# DAQAccel.net
KiCad netlist of a schematic drawn in EAGLE
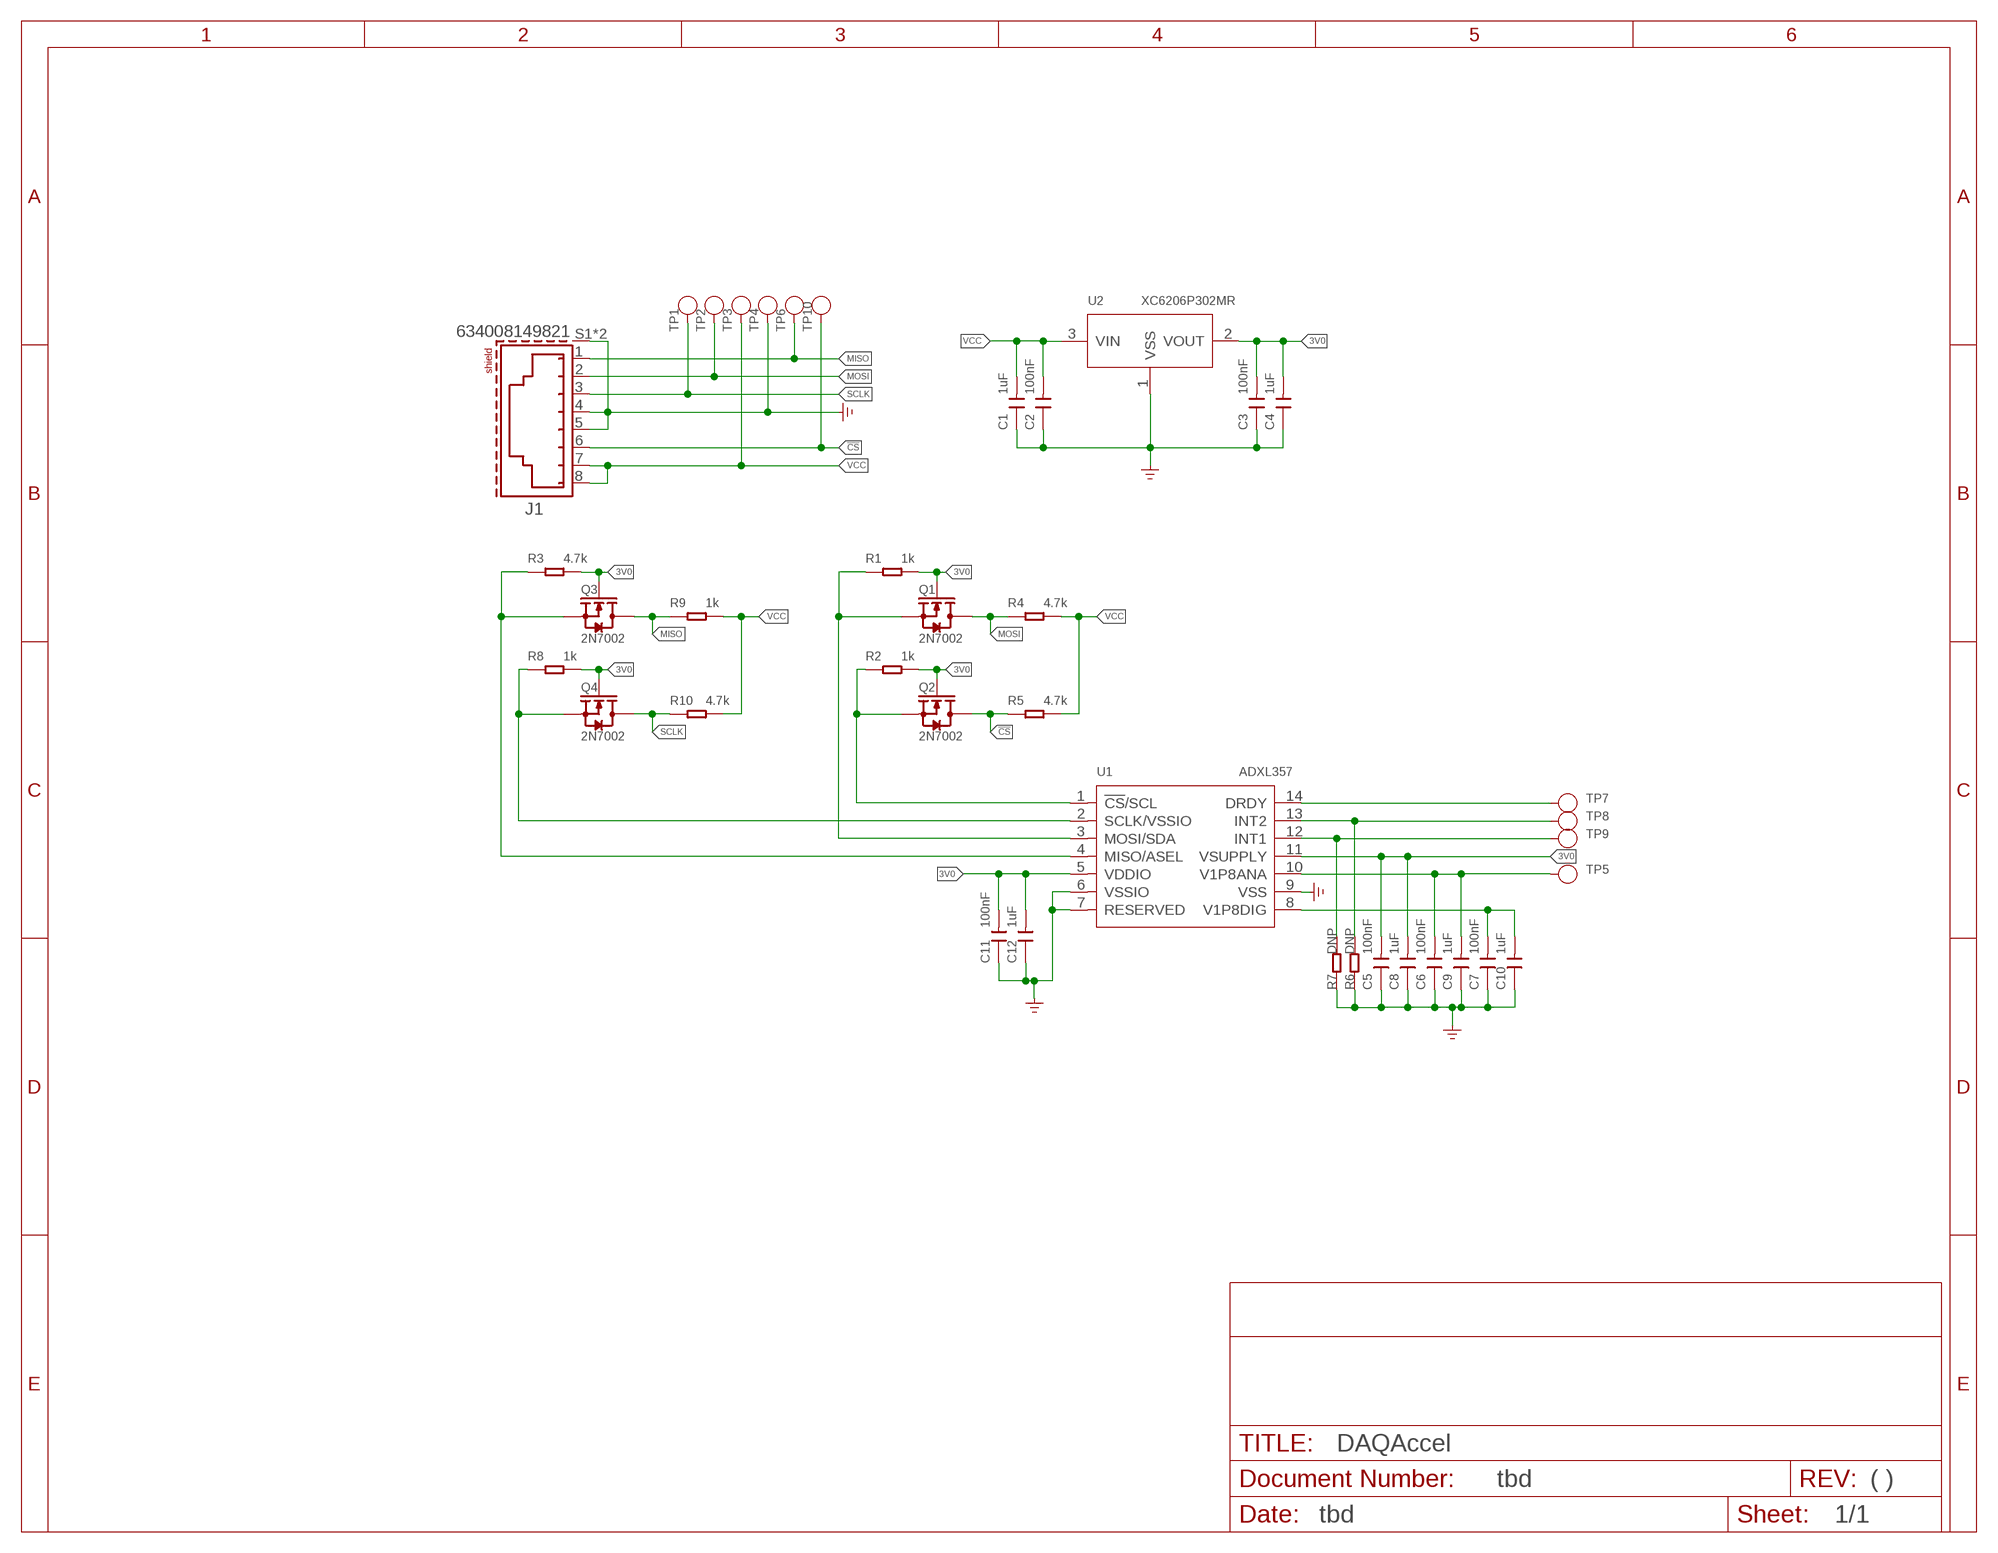
[diagram p0: schematic, sheet 1]

(export (version "E")
  (design (tool "Eeschema 10.0.6"))
  (components
    (comp (ref "C1")
      (value "1uF")
      (footprint "eagle-import:C0603")
      (libsource (lib "eagle-import") (part "CAP-0603"))
    )
    (comp (ref "C2")
      (value "100nF")
      (footprint "eagle-import:C0603")
      (libsource (lib "eagle-import") (part "CAP-0603"))
    )
    (comp (ref "C3")
      (value "100nF")
      (footprint "eagle-import:C0603")
      (libsource (lib "eagle-import") (part "CAP-0603"))
    )
    (comp (ref "C4")
      (value "1uF")
      (footprint "eagle-import:C0603")
      (libsource (lib "eagle-import") (part "CAP-0603"))
    )
    (comp (ref "C5")
      (value "100nF")
      (footprint "eagle-import:C0603")
      (libsource (lib "eagle-import") (part "CAP-0603"))
    )
    (comp (ref "C6")
      (value "100nF")
      (footprint "eagle-import:C0603")
      (libsource (lib "eagle-import") (part "CAP-0603"))
    )
    (comp (ref "C7")
      (value "100nF")
      (footprint "eagle-import:C0603")
      (libsource (lib "eagle-import") (part "CAP-0603"))
    )
    (comp (ref "C8")
      (value "1uF")
      (footprint "eagle-import:C0603")
      (libsource (lib "eagle-import") (part "CAP-0603"))
    )
    (comp (ref "C9")
      (value "1uF")
      (footprint "eagle-import:C0603")
      (libsource (lib "eagle-import") (part "CAP-0603"))
    )
    (comp (ref "C10")
      (value "1uF")
      (footprint "eagle-import:C0603")
      (libsource (lib "eagle-import") (part "CAP-0603"))
    )
    (comp (ref "C11")
      (value "100nF")
      (footprint "eagle-import:C0603")
      (libsource (lib "eagle-import") (part "CAP-0603"))
    )
    (comp (ref "C12")
      (value "1uF")
      (footprint "eagle-import:C0603")
      (libsource (lib "eagle-import") (part "CAP-0603"))
    )
    (comp (ref "J1")
      (value "634008149821")
      (footprint "eagle-import:634008149821")
      (libsource (lib "eagle-import") (part "634008149821"))
    )
    (comp (ref "Q1")
      (value "2N7002")
      (footprint "eagle-import:SOT-23")
      (libsource (lib "eagle-import") (part "MOSFET-N'SOT23'"))
    )
    (comp (ref "Q2")
      (value "2N7002")
      (footprint "eagle-import:SOT-23")
      (libsource (lib "eagle-import") (part "MOSFET-N'SOT23'"))
    )
    (comp (ref "Q3")
      (value "2N7002")
      (footprint "eagle-import:SOT-23")
      (libsource (lib "eagle-import") (part "MOSFET-N'SOT23'"))
    )
    (comp (ref "Q4")
      (value "2N7002")
      (footprint "eagle-import:SOT-23")
      (libsource (lib "eagle-import") (part "MOSFET-N'SOT23'"))
    )
    (comp (ref "R1")
      (value "1k")
      (footprint "eagle-import:R0603")
      (libsource (lib "eagle-import") (part "RES-0603"))
    )
    (comp (ref "R2")
      (value "1k")
      (footprint "eagle-import:R0603")
      (libsource (lib "eagle-import") (part "RES-0603"))
    )
    (comp (ref "R3")
      (value "4.7k")
      (footprint "eagle-import:R0603")
      (libsource (lib "eagle-import") (part "RES-0603"))
    )
    (comp (ref "R4")
      (value "4.7k")
      (footprint "eagle-import:R0603")
      (libsource (lib "eagle-import") (part "RES-0603"))
    )
    (comp (ref "R5")
      (value "4.7k")
      (footprint "eagle-import:R0603")
      (libsource (lib "eagle-import") (part "RES-0603"))
    )
    (comp (ref "R6")
      (value "DNP")
      (footprint "eagle-import:R0603")
      (libsource (lib "eagle-import") (part "RES-0603"))
    )
    (comp (ref "R7")
      (value "DNP")
      (footprint "eagle-import:R0603")
      (libsource (lib "eagle-import") (part "RES-0603"))
    )
    (comp (ref "R8")
      (value "1k")
      (footprint "eagle-import:R0603")
      (libsource (lib "eagle-import") (part "RES-0603"))
    )
    (comp (ref "R9")
      (value "1k")
      (footprint "eagle-import:R0603")
      (libsource (lib "eagle-import") (part "RES-0603"))
    )
    (comp (ref "R10")
      (value "4.7k")
      (footprint "eagle-import:R0603")
      (libsource (lib "eagle-import") (part "RES-0603"))
    )
    (comp (ref "TP1")
      (value "Test")
      (footprint "eagle-import:TP-D45MIL")
      (fields (field (name "PARTNO") "DNP"))
      (libsource (lib "eagle-import") (part "TEST-POINT'4545'"))
    )
    (comp (ref "TP2")
      (value "Test")
      (footprint "eagle-import:TP-D45MIL")
      (fields (field (name "PARTNO") "DNP"))
      (libsource (lib "eagle-import") (part "TEST-POINT'4545'"))
    )
    (comp (ref "TP3")
      (value "Test")
      (footprint "eagle-import:TP-D45MIL")
      (fields (field (name "PARTNO") "DNP"))
      (libsource (lib "eagle-import") (part "TEST-POINT'4545'"))
    )
    (comp (ref "TP4")
      (value "Test")
      (footprint "eagle-import:TP-D45MIL")
      (fields (field (name "PARTNO") "DNP"))
      (libsource (lib "eagle-import") (part "TEST-POINT'4545'"))
    )
    (comp (ref "TP5")
      (value "Test")
      (footprint "eagle-import:TP-D45MIL")
      (fields (field (name "PARTNO") "DNP"))
      (libsource (lib "eagle-import") (part "TEST-POINT'4545'"))
    )
    (comp (ref "TP6")
      (value "Test")
      (footprint "eagle-import:TP-D45MIL")
      (fields (field (name "PARTNO") "DNP"))
      (libsource (lib "eagle-import") (part "TEST-POINT'4545'"))
    )
    (comp (ref "TP7")
      (value "Test")
      (footprint "eagle-import:TP-D45MIL")
      (fields (field (name "PARTNO") "DNP"))
      (libsource (lib "eagle-import") (part "TEST-POINT'4545'"))
    )
    (comp (ref "TP8")
      (value "Test")
      (footprint "eagle-import:TP-D45MIL")
      (fields (field (name "PARTNO") "DNP"))
      (libsource (lib "eagle-import") (part "TEST-POINT'4545'"))
    )
    (comp (ref "TP9")
      (value "Test")
      (footprint "eagle-import:TP-D45MIL")
      (fields (field (name "PARTNO") "DNP"))
      (libsource (lib "eagle-import") (part "TEST-POINT'4545'"))
    )
    (comp (ref "TP10")
      (value "Test")
      (footprint "eagle-import:TP-D45MIL")
      (fields (field (name "PARTNO") "DNP"))
      (libsource (lib "eagle-import") (part "TEST-POINT'4545'"))
    )
    (comp (ref "U1")
      (value "ADXL357")
      (footprint "eagle-import:LCC-14-TERMINAL")
      (libsource (lib "eagle-import") (part "SENSOR-ADXL357BEZ"))
    )
    (comp (ref "U2")
      (value "XC6206P302MR")
      (footprint "eagle-import:SOT-23")
      (libsource (lib "eagle-import") (part "PMIC-XC6206PMR"))
    )
  )
  (nets
    (net (code "1") (name "/~{CS}") (class "Default")
      (node (ref "J1") (pin "6") (pinfunction "6_6") (pintype "passive"))
      (node (ref "Q2") (pin "3") (pinfunction "D_3") (pintype "passive"))
      (node (ref "R5") (pin "1") (pinfunction "1_1") (pintype "passive"))
      (node (ref "TP10") (pin "T") (pinfunction "T_T") (pintype "bidirectional"))
    )
    (net (code "2") (name "3V0") (class "Default")
      (node (ref "C11") (pin "2") (pinfunction "2_2") (pintype "passive"))
      (node (ref "C12") (pin "2") (pinfunction "2_2") (pintype "passive"))
      (node (ref "C3") (pin "2") (pinfunction "2_2") (pintype "passive"))
      (node (ref "C4") (pin "2") (pinfunction "2_2") (pintype "passive"))
      (node (ref "C5") (pin "2") (pinfunction "2_2") (pintype "passive"))
      (node (ref "C8") (pin "2") (pinfunction "2_2") (pintype "passive"))
      (node (ref "Q1") (pin "1") (pinfunction "G_1") (pintype "passive"))
      (node (ref "Q2") (pin "1") (pinfunction "G_1") (pintype "passive"))
      (node (ref "Q3") (pin "1") (pinfunction "G_1") (pintype "passive"))
      (node (ref "Q4") (pin "1") (pinfunction "G_1") (pintype "passive"))
      (node (ref "R1") (pin "2") (pinfunction "2_2") (pintype "passive"))
      (node (ref "R2") (pin "2") (pinfunction "2_2") (pintype "passive"))
      (node (ref "R3") (pin "2") (pinfunction "2_2") (pintype "passive"))
      (node (ref "R8") (pin "2") (pinfunction "2_2") (pintype "passive"))
      (node (ref "U1") (pin "11") (pinfunction "VSUPPLY_11") (pintype "bidirectional"))
      (node (ref "U1") (pin "5") (pinfunction "VDDIO_5") (pintype "bidirectional"))
      (node (ref "U2") (pin "2") (pinfunction "VOUT_2") (pintype "bidirectional"))
    )
    (net (code "3") (name "GND_POWER") (class "Default")
      (node (ref "C1") (pin "1") (pinfunction "1_1") (pintype "passive"))
      (node (ref "C10") (pin "1") (pinfunction "1_1") (pintype "passive"))
      (node (ref "C11") (pin "1") (pinfunction "1_1") (pintype "passive"))
      (node (ref "C12") (pin "1") (pinfunction "1_1") (pintype "passive"))
      (node (ref "C2") (pin "1") (pinfunction "1_1") (pintype "passive"))
      (node (ref "C3") (pin "1") (pinfunction "1_1") (pintype "passive"))
      (node (ref "C4") (pin "1") (pinfunction "1_1") (pintype "passive"))
      (node (ref "C5") (pin "1") (pinfunction "1_1") (pintype "passive"))
      (node (ref "C6") (pin "1") (pinfunction "1_1") (pintype "passive"))
      (node (ref "C7") (pin "1") (pinfunction "1_1") (pintype "passive"))
      (node (ref "C8") (pin "1") (pinfunction "1_1") (pintype "passive"))
      (node (ref "C9") (pin "1") (pinfunction "1_1") (pintype "passive"))
      (node (ref "J1") (pin "4") (pinfunction "4_4") (pintype "passive"))
      (node (ref "J1") (pin "5") (pinfunction "5_5") (pintype "passive"))
      (node (ref "J1") (pin "S1") (pinfunction "SHIELD_S1") (pintype "passive"))
      (node (ref "J1") (pin "S2") (pinfunction "SHIELD_S2") (pintype "passive"))
      (node (ref "R6") (pin "1") (pinfunction "1_1") (pintype "passive"))
      (node (ref "R7") (pin "1") (pinfunction "1_1") (pintype "passive"))
      (node (ref "TP4") (pin "T") (pinfunction "T_T") (pintype "bidirectional"))
      (node (ref "U1") (pin "6") (pinfunction "VSSIO_6") (pintype "bidirectional"))
      (node (ref "U1") (pin "7") (pinfunction "RESERVED_7") (pintype "bidirectional"))
      (node (ref "U1") (pin "9") (pinfunction "VSS_9") (pintype "bidirectional"))
      (node (ref "U2") (pin "1") (pinfunction "VSS_1") (pintype "bidirectional"))
    )
    (net (code "4") (name "MISO") (class "Default")
      (node (ref "J1") (pin "1") (pinfunction "1_1") (pintype "passive"))
      (node (ref "Q3") (pin "3") (pinfunction "D_3") (pintype "passive"))
      (node (ref "R9") (pin "1") (pinfunction "1_1") (pintype "passive"))
      (node (ref "TP6") (pin "T") (pinfunction "T_T") (pintype "bidirectional"))
    )
    (net (code "5") (name "MOSI") (class "Default")
      (node (ref "J1") (pin "2") (pinfunction "2_2") (pintype "passive"))
      (node (ref "Q1") (pin "3") (pinfunction "D_3") (pintype "passive"))
      (node (ref "R4") (pin "1") (pinfunction "1_1") (pintype "passive"))
      (node (ref "TP2") (pin "T") (pinfunction "T_T") (pintype "bidirectional"))
    )
    (net (code "6") (name "Net-(Q1-S)") (class "Default")
      (node (ref "Q1") (pin "2") (pinfunction "S_2") (pintype "passive"))
      (node (ref "R1") (pin "1") (pinfunction "1_1") (pintype "passive"))
      (node (ref "U1") (pin "3") (pinfunction "MOSI/SDA_3") (pintype "bidirectional"))
    )
    (net (code "7") (name "Net-(Q2-S)") (class "Default")
      (node (ref "Q2") (pin "2") (pinfunction "S_2") (pintype "passive"))
      (node (ref "R2") (pin "1") (pinfunction "1_1") (pintype "passive"))
      (node (ref "U1") (pin "1") (pinfunction "~{CS}/SCL_1") (pintype "bidirectional"))
    )
    (net (code "8") (name "Net-(Q3-S)") (class "Default")
      (node (ref "Q3") (pin "2") (pinfunction "S_2") (pintype "passive"))
      (node (ref "R3") (pin "1") (pinfunction "1_1") (pintype "passive"))
      (node (ref "U1") (pin "4") (pinfunction "MISO/ASEL_4") (pintype "bidirectional"))
    )
    (net (code "9") (name "Net-(Q4-S)") (class "Default")
      (node (ref "Q4") (pin "2") (pinfunction "S_2") (pintype "passive"))
      (node (ref "R8") (pin "1") (pinfunction "1_1") (pintype "passive"))
      (node (ref "U1") (pin "2") (pinfunction "SCLK/VSSIO_2") (pintype "bidirectional"))
    )
    (net (code "10") (name "Net-(U1-DRDY)") (class "Default")
      (node (ref "TP7") (pin "T") (pinfunction "T_T") (pintype "bidirectional"))
      (node (ref "U1") (pin "14") (pinfunction "DRDY_14") (pintype "bidirectional"))
    )
    (net (code "11") (name "Net-(U1-INT1)") (class "Default")
      (node (ref "R7") (pin "2") (pinfunction "2_2") (pintype "passive"))
      (node (ref "TP9") (pin "T") (pinfunction "T_T") (pintype "bidirectional"))
      (node (ref "U1") (pin "12") (pinfunction "INT1_12") (pintype "bidirectional"))
    )
    (net (code "12") (name "Net-(U1-INT2)") (class "Default")
      (node (ref "R6") (pin "2") (pinfunction "2_2") (pintype "passive"))
      (node (ref "TP8") (pin "T") (pinfunction "T_T") (pintype "bidirectional"))
      (node (ref "U1") (pin "13") (pinfunction "INT2_13") (pintype "bidirectional"))
    )
    (net (code "13") (name "Net-(U1-V1P8ANA)") (class "Default")
      (node (ref "C6") (pin "2") (pinfunction "2_2") (pintype "passive"))
      (node (ref "C9") (pin "2") (pinfunction "2_2") (pintype "passive"))
      (node (ref "TP5") (pin "T") (pinfunction "T_T") (pintype "bidirectional"))
      (node (ref "U1") (pin "10") (pinfunction "V1P8ANA_10") (pintype "bidirectional"))
    )
    (net (code "14") (name "Net-(U1-V1P8DIG)") (class "Default")
      (node (ref "C10") (pin "2") (pinfunction "2_2") (pintype "passive"))
      (node (ref "C7") (pin "2") (pinfunction "2_2") (pintype "passive"))
      (node (ref "U1") (pin "8") (pinfunction "V1P8DIG_8") (pintype "bidirectional"))
    )
    (net (code "15") (name "SCLK") (class "Default")
      (node (ref "J1") (pin "3") (pinfunction "3_3") (pintype "passive"))
      (node (ref "Q4") (pin "3") (pinfunction "D_3") (pintype "passive"))
      (node (ref "R10") (pin "1") (pinfunction "1_1") (pintype "passive"))
      (node (ref "TP1") (pin "T") (pinfunction "T_T") (pintype "bidirectional"))
    )
    (net (code "16") (name "VCC") (class "Default")
      (node (ref "C1") (pin "2") (pinfunction "2_2") (pintype "passive"))
      (node (ref "C2") (pin "2") (pinfunction "2_2") (pintype "passive"))
      (node (ref "J1") (pin "7") (pinfunction "7_7") (pintype "passive"))
      (node (ref "J1") (pin "8") (pinfunction "8_8") (pintype "passive"))
      (node (ref "R10") (pin "2") (pinfunction "2_2") (pintype "passive"))
      (node (ref "R4") (pin "2") (pinfunction "2_2") (pintype "passive"))
      (node (ref "R5") (pin "2") (pinfunction "2_2") (pintype "passive"))
      (node (ref "R9") (pin "2") (pinfunction "2_2") (pintype "passive"))
      (node (ref "TP3") (pin "T") (pinfunction "T_T") (pintype "bidirectional"))
      (node (ref "U2") (pin "3") (pinfunction "VIN_3") (pintype "bidirectional"))
    )
  )
)
